# OK1050-C_V1_2_TFcard.net
KiCad netlist of a schematic drawn in Altium Designer
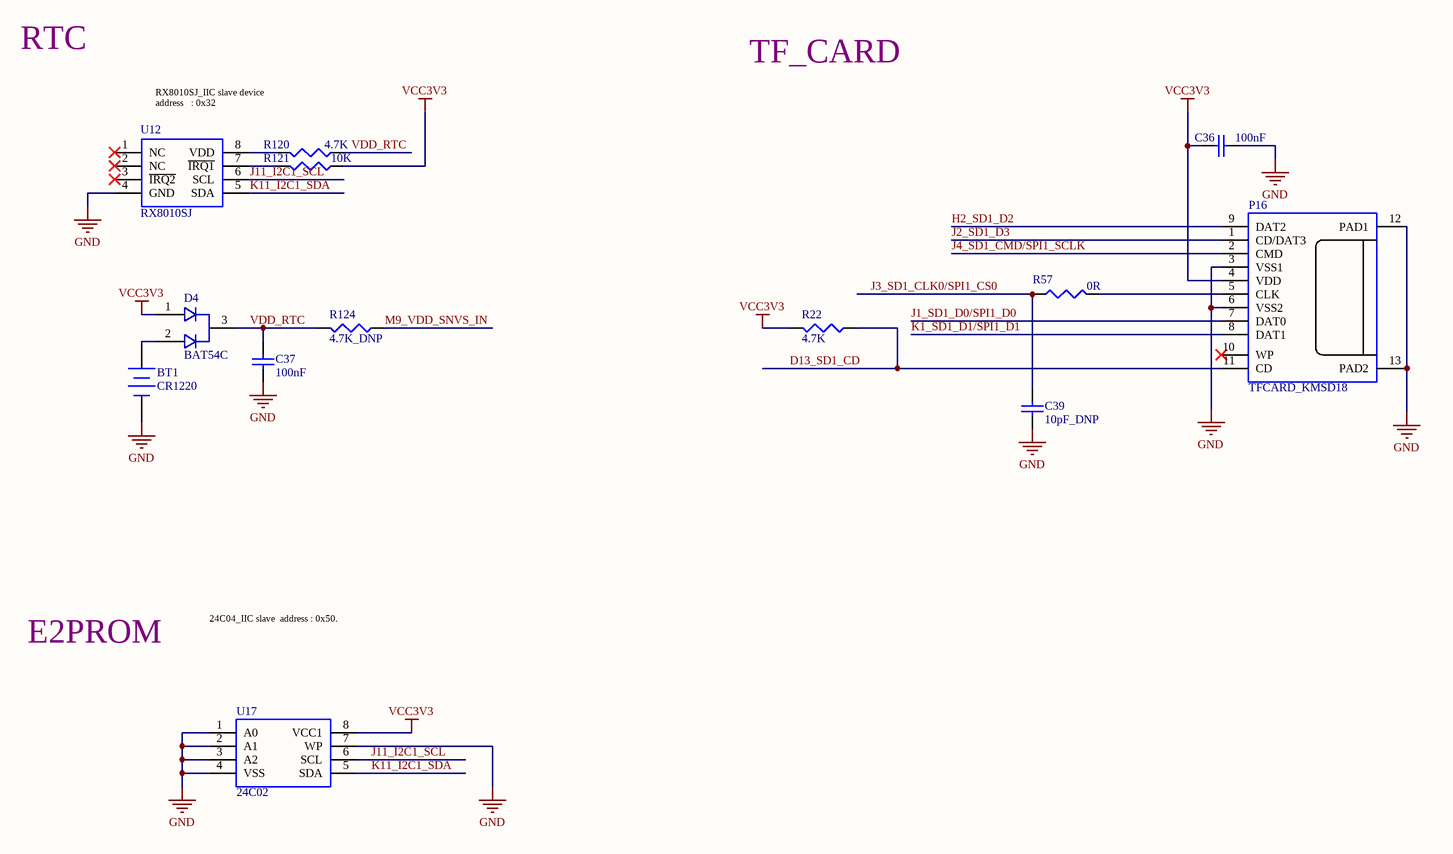
[diagram p0: OK1050-C_V1.2_TFcard.SchDoc]

(export (version "E")
  (design (tool "Eeschema 10.0.6"))
  (components
    (comp (ref "BT1")
      (value "CR1220")
      (footprint "BH-1220 BATTERY")
      (description "Multicell Battery")
      (fields (field (name "PUBLISHER") "Altium Limited"))
      (libsource (lib "Miscellaneous Devices") (part "Battery"))
    )
    (comp (ref "C36")
      (value "100nF")
      (footprint "0603C+")
      (description "Capacitor")
      (fields (field (name "PUBLISHER") "Altium Limited"))
      (libsource (lib "Miscellaneous Devices") (part "Cap"))
    )
    (comp (ref "C37")
      (value "100nF")
      (footprint "0603C+")
      (description "Capacitor")
      (fields (field (name "PUBLISHER") "Altium Limited"))
      (libsource (lib "Miscellaneous Devices") (part "Cap"))
    )
    (comp (ref "C39")
      (value "10pF_DNP")
      (footprint "0603C+")
      (description "Capacitor")
      (fields (field (name "PUBLISHER") "Altium Limited"))
      (libsource (lib "Miscellaneous Devices") (part "Cap"))
    )
    (comp (ref "D4") (value "BAT54C") (footprint "SOT23") (libsource (lib "Sch") (part "BAT54C")))
    (comp (ref "P16")
      (value "TFCARD_KMSD18")
      (footprint "TF-CARD")
      (libsource (lib "IMX6QP") (part "SDCARD_KMSD18"))
    )
    (comp (ref "R22")
      (value "4.7K")
      (footprint "0603R+")
      (description "Resistor")
      (fields (field (name "PUBLISHER") "Altium Limited"))
      (libsource (lib "Miscellaneous Devices") (part "Res3"))
    )
    (comp (ref "R57")
      (value "0R")
      (footprint "0603R+")
      (description "Resistor")
      (fields (field (name "PUBLISHER") "Altium Limited"))
      (libsource (lib "Miscellaneous Devices") (part "Res3"))
    )
    (comp (ref "R120")
      (value "4.7K")
      (footprint "0603R+")
      (description "Resistor")
      (fields (field (name "PUBLISHER") "Altium Limited"))
      (libsource (lib "Miscellaneous Devices") (part "Res3"))
    )
    (comp (ref "R121")
      (value "10K")
      (footprint "0603R+")
      (description "Resistor")
      (fields (field (name "PUBLISHER") "Altium Limited"))
      (libsource (lib "Miscellaneous Devices") (part "Res3"))
    )
    (comp (ref "R124")
      (value "4.7K_DNP")
      (footprint "0603R+")
      (description "Resistor")
      (fields (field (name "PUBLISHER") "Altium Limited"))
      (libsource (lib "Miscellaneous Devices") (part "Res3"))
    )
    (comp (ref "U12") (value "RX8010SJ") (footprint "RX8010SJ") (libsource (lib "Sch") (part "RX8010SJ")))
    (comp (ref "U17")
      (value "24C02")
      (footprint "24C04_SO8")
      (libsource (lib "PCB_RT1052") (part "24C04_SO8"))
    )
  )
  (nets
    (net (code "1") (name "/D13_SD1_CD") (class "Default")
      (node (ref "P16") (pin "11") (pinfunction "CD_11") (pintype "passive"))
      (node (ref "R22") (pin "1") (pinfunction "1_1") (pintype "passive"))
    )
    (net (code "2") (name "/H2_SD1_D2") (class "Default")
      (node (ref "P16") (pin "9") (pinfunction "DAT2_9") (pintype "passive"))
    )
    (net (code "3") (name "/J1_SD1_D0{slash}SPI1_D0") (class "Default")
      (node (ref "P16") (pin "7") (pinfunction "DAT0_7") (pintype "passive"))
    )
    (net (code "4") (name "/J2_SD1_D3") (class "Default")
      (node (ref "P16") (pin "1") (pinfunction "CD/DAT3_1") (pintype "passive"))
    )
    (net (code "5") (name "/J3_SD1_CLK0{slash}SPI1_CS0") (class "Default")
      (node (ref "C39") (pin "1") (pinfunction "1_1") (pintype "passive"))
      (node (ref "R57") (pin "1") (pinfunction "1_1") (pintype "passive"))
    )
    (net (code "6") (name "/J4_SD1_CMD{slash}SPI1_SCLK") (class "Default")
      (node (ref "P16") (pin "2") (pinfunction "CMD_2") (pintype "passive"))
    )
    (net (code "7") (name "/J11_I2C1_SCL") (class "Default")
      (node (ref "U12") (pin "6") (pinfunction "SCL_6") (pintype "passive"))
      (node (ref "U17") (pin "6") (pinfunction "SCL_6") (pintype "passive"))
    )
    (net (code "8") (name "/K1_SD1_D1{slash}SPI1_D1") (class "Default")
      (node (ref "P16") (pin "8") (pinfunction "DAT1_8") (pintype "passive"))
    )
    (net (code "9") (name "/K11_I2C1_SDA") (class "Default")
      (node (ref "U12") (pin "5") (pinfunction "SDA_5") (pintype "passive"))
      (node (ref "U17") (pin "5") (pinfunction "SDA_5") (pintype "passive"))
    )
    (net (code "10") (name "/M9_VDD_SNVS_IN") (class "Default")
      (node (ref "R124") (pin "1") (pinfunction "1_1") (pintype "passive"))
    )
    (net (code "11") (name "/VDD_RTC") (class "Default")
      (node (ref "C37") (pin "2") (pinfunction "2_2") (pintype "passive"))
      (node (ref "D4") (pin "3") (pintype "passive"))
      (node (ref "R120") (pin "1") (pinfunction "1_1") (pintype "passive"))
      (node (ref "R124") (pin "2") (pinfunction "2_2") (pintype "passive"))
    )
    (net (code "12") (name "GND") (class "Default")
      (node (ref "BT1") (pin "2") (pinfunction "-_2") (pintype "passive"))
      (node (ref "C36") (pin "1") (pinfunction "1_1") (pintype "passive"))
      (node (ref "C37") (pin "1") (pinfunction "1_1") (pintype "passive"))
      (node (ref "C39") (pin "2") (pinfunction "2_2") (pintype "passive"))
      (node (ref "P16") (pin "12") (pinfunction "PAD1_12") (pintype "passive"))
      (node (ref "P16") (pin "13") (pinfunction "PAD2_13") (pintype "passive"))
      (node (ref "P16") (pin "3") (pinfunction "VSS1_3") (pintype "passive"))
      (node (ref "P16") (pin "6") (pinfunction "VSS2_6") (pintype "passive"))
      (node (ref "U12") (pin "4") (pinfunction "GND_4") (pintype "passive"))
      (node (ref "U17") (pin "1") (pinfunction "A0_1") (pintype "passive"))
      (node (ref "U17") (pin "2") (pinfunction "A1_2") (pintype "passive"))
      (node (ref "U17") (pin "3") (pinfunction "A2_3") (pintype "passive"))
      (node (ref "U17") (pin "4") (pinfunction "VSS_4") (pintype "passive"))
      (node (ref "U17") (pin "7") (pinfunction "WP_7") (pintype "passive"))
    )
    (net (code "13") (name "Net-(BT1-+)") (class "Default")
      (node (ref "BT1") (pin "1") (pinfunction "+_1") (pintype "passive"))
      (node (ref "D4") (pin "2") (pinfunction "2_2") (pintype "passive"))
    )
    (net (code "14") (name "Net-(P16-CLK)") (class "Default")
      (node (ref "P16") (pin "5") (pinfunction "CLK_5") (pintype "passive"))
      (node (ref "R57") (pin "2") (pinfunction "2_2") (pintype "passive"))
    )
    (net (code "15") (name "Net-(U12-VDD)") (class "Default")
      (node (ref "R120") (pin "2") (pinfunction "2_2") (pintype "passive"))
      (node (ref "U12") (pin "8") (pinfunction "VDD_8") (pintype "passive"))
    )
    (net (code "16") (name "Net-(U12-~{IRQ1})") (class "Default")
      (node (ref "R121") (pin "2") (pinfunction "2_2") (pintype "passive"))
      (node (ref "U12") (pin "7") (pinfunction "~{IRQ1}_7") (pintype "passive"))
    )
    (net (code "17") (name "VCC3V3") (class "Default")
      (node (ref "C36") (pin "2") (pinfunction "2_2") (pintype "passive"))
      (node (ref "D4") (pin "1") (pinfunction "1_1") (pintype "passive"))
      (node (ref "P16") (pin "4") (pinfunction "VDD_4") (pintype "passive"))
      (node (ref "R121") (pin "1") (pinfunction "1_1") (pintype "passive"))
      (node (ref "R22") (pin "2") (pinfunction "2_2") (pintype "passive"))
      (node (ref "U17") (pin "8") (pinfunction "VCC1_8") (pintype "passive"))
    )
    (net (code "18") (name "unconnected-(P16-WP-Pad10)") (class "Default")
      (node (ref "P16") (pin "10") (pinfunction "WP_10") (pintype "passive+no_connect"))
    )
    (net (code "19") (name "unconnected-(U12-NC-Pad1)") (class "Default")
      (node (ref "U12") (pin "1") (pinfunction "NC_1") (pintype "passive+no_connect"))
    )
    (net (code "20") (name "unconnected-(U12-NC-Pad2)") (class "Default")
      (node (ref "U12") (pin "2") (pinfunction "NC_2") (pintype "passive+no_connect"))
    )
    (net (code "21") (name "unconnected-(U12-~{IRQ2}-Pad3)") (class "Default")
      (node (ref "U12") (pin "3") (pinfunction "~{IRQ2}_3") (pintype "passive+no_connect"))
    )
  )
)
